# 9-Other_Inputs.net
KiCad netlist of a schematic drawn in Altium Designer
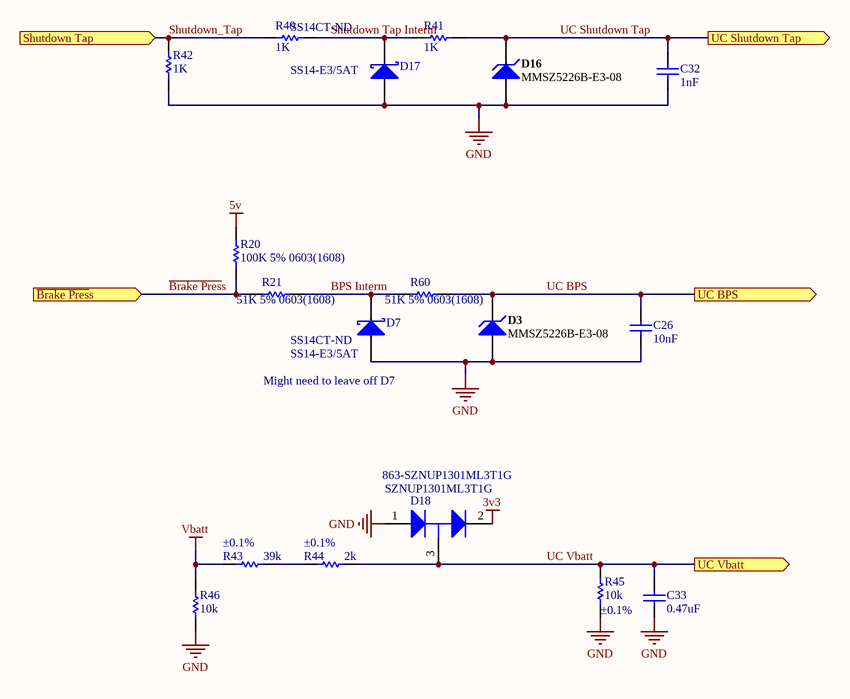
[diagram p0: 9-Other_Inputs.SchDoc]

(export (version "E")
  (design (tool "Eeschema 10.0.6"))
  (components
    (comp (ref "C26")
      (value "10nF")
      (footprint "1608[0603]")
      (description "Capacitor")
      (fields
        (field (name "MANUFACTURER") "Yageo")
        (field (name "MANUFACTURER PART NUMBER") "CC0603KRX7R9BB104")
      )
      (libsource (lib "Miscellaneous Devices") (part "Cap"))
    )
    (comp (ref "C32")
      (value "1nF")
      (footprint "1608[0603]")
      (description "Capacitor")
      (fields
        (field (name "MANUFACTURER") "Yageo")
        (field (name "MANUFACTURER PART NUMBER") "CC0603KRX7R9BB102")
      )
      (libsource (lib "Miscellaneous Devices") (part "Cap"))
    )
    (comp (ref "C33")
      (value "0.47uF")
      (footprint "1608[0603]")
      (description "Capacitor")
      (fields
        (field (name "MANUFACTURER") "Yageo")
        (field (name "MANUFACTURER PART NUMBER") "CC0603KRX7R8BB474")
      )
      (libsource (lib "Miscellaneous Devices") (part "Cap"))
    )
    (comp (ref "D3")
      (value "MMSZ5226B-E3-08")
      (footprint "VISH-SOD-123-2_V")
      (description "Small Signal Zener Diode, 3.3 V +/- 5%, -55 to 155 degC, 2-Pin SOD-123, RoHS, Tape and Reel")
      (fields (field (name "TOLERANCE") "+/- 5%") (field (name "MANUFACTURER") "Vishay Semiconductor"))
      (libsource (lib "Altium Content Vault") (part "VISH-DZEN_A1K2-2"))
    )
    (comp (ref "D7")
      (value "SS14-E3/5AT")
      (footprint "VISH-DO-214AC-2_V")
      (fields
        (field (name "MANUFACTURER") "Vishay Semiconductor")
        (field (name "SUPPLIER PART NUMBER 1") "SS14CT-ND")
      )
      (libsource (lib "Altium Content Vault") (part "VISH-DSKY_A1K2-2"))
    )
    (comp (ref "D16")
      (value "MMSZ5226B-E3-08")
      (footprint "VISH-SOD-123-2_V")
      (description "Small Signal Zener Diode, 3.3 V +/- 5%, -55 to 155 degC, 2-Pin SOD-123, RoHS, Tape and Reel")
      (fields (field (name "TOLERANCE") "+/- 5%") (field (name "MANUFACTURER") "Vishay Semiconductor"))
      (libsource (lib "Altium Content Vault") (part "VISH-DZEN_A1K2-2"))
    )
    (comp (ref "D17")
      (value "SS14-E3/5AT")
      (footprint "VISH-DO-214AC-2_V")
      (fields
        (field (name "MANUFACTURER") "Vishay Semiconductor")
        (field (name "SUPPLIER PART NUMBER 1") "SS14CT-ND")
      )
      (libsource (lib "Altium Content Vault") (part "VISH-DSKY_A1K2-2"))
    )
    (comp (ref "D18")
      (value "SZNUP1301ML3T1G")
      (footprint "ONSC-SOT-23-3-318-08_V")
      (fields
        (field (name "MANUFACTURER") "On Semiconductor")
        (field (name "SUPPLIER PART NUMBER 1") "863-SZNUP1301ML3T1G")
      )
      (libsource (lib "Altium Content Vault") (part "ONSC-NUP1301-SOT-23-3-318-08"))
    )
    (comp (ref "R20")
      (value "100K 5% 0603(1608)")
      (footprint "RESC0603(1608)_N")
      (description "100K 0.1W 5% 0603 (1608 Metric)  SMD")
      (fields (field (name "TOLERANCE") "5 %") (field (name "POWER") "0.1 W"))
      (libsource (lib "Altium Content Vault") (part "RES"))
    )
    (comp (ref "R21")
      (value "51K 5% 0603(1608)")
      (footprint "RESC0603(1608)_N")
      (description "51K 0.1W 5% 0603 (1608 Metric)  SMD")
      (fields (field (name "POWER") "0.1 W") (field (name "TOLERANCE") "5 %"))
      (libsource (lib "Altium Content Vault") (part "RES"))
    )
    (comp (ref "R40")
      (value "1K")
      (footprint "1608[0603]")
      (description "Resistor")
      (fields
        (field (name "MANUFACTURER") "Panasonic Electronic Components")
        (field (name "MANUFACTURER PART NUMBER") "ERJ-PA3F1001V")
      )
      (libsource (lib "Miscellaneous Devices") (part "Res1"))
    )
    (comp (ref "R41")
      (value "1K")
      (footprint "1608[0603]")
      (description "Resistor")
      (fields
        (field (name "MANUFACTURER") "Panasonic Electronic Components")
        (field (name "MANUFACTURER PART NUMBER") "ERJ-PA3F1001V")
      )
      (libsource (lib "Miscellaneous Devices") (part "Res1"))
    )
    (comp (ref "R42")
      (value "1K")
      (footprint "1608[0603]")
      (description "Resistor")
      (fields
        (field (name "MANUFACTURER") "Panasonic Electronic Components")
        (field (name "MANUFACTURER PART NUMBER") "ERJ-PA3F1001V")
      )
      (libsource (lib "Miscellaneous Devices") (part "Res1"))
    )
    (comp (ref "R43")
      (value "39k")
      (footprint "1608[0603]")
      (description "Resistor")
      (fields
        (field (name "MANUFACTURER") "Yageo")
        (field (name "MANUFACTURER PART NUMBER") "RT0603BRD0739KL")
        (field (name "TOLERANCE") "±0.1%")
      )
      (libsource (lib "Miscellaneous Devices") (part "Res1"))
    )
    (comp (ref "R44")
      (value "2k")
      (footprint "1608[0603]")
      (description "Resistor")
      (fields
        (field (name "MANUFACTURER") "Yageo")
        (field (name "MANUFACTURER PART NUMBER") "AT0603BRD072KL")
        (field (name "TOLERANCE") "±0.1%")
      )
      (libsource (lib "Miscellaneous Devices") (part "Res1"))
    )
    (comp (ref "R45")
      (value "10k")
      (footprint "1608[0603]")
      (description "Resistor")
      (fields
        (field (name "MANUFACTURER") "Yageo")
        (field (name "MANUFACTURER PART NUMBER") "RT0603BRD0710KL")
        (field (name "TOLERANCE") "±0.1%")
      )
      (libsource (lib "Miscellaneous Devices") (part "Res1"))
    )
    (comp (ref "R46")
      (value "10k")
      (footprint "1608[0603]")
      (description "Resistor")
      (fields
        (field (name "MANUFACTURER") "Yageo")
        (field (name "MANUFACTURER PART NUMBER") "RC0603JR-0710KL")
      )
      (libsource (lib "Miscellaneous Devices") (part "Res1"))
    )
    (comp (ref "R60")
      (value "51K 5% 0603(1608)")
      (footprint "RESC0603(1608)_N")
      (description "51K 0.1W 5% 0603 (1608 Metric)  SMD")
      (fields (field (name "POWER") "0.1 W") (field (name "TOLERANCE") "5 %"))
      (libsource (lib "Altium Content Vault") (part "RES"))
    )
  )
  (nets
    (net (code "1") (name "/BPS Interm") (class "Default")
      (node (ref "D7") (pin "2") (pinfunction "K_2") (pintype "passive"))
      (node (ref "R21") (pin "2") (pinfunction "2_2") (pintype "passive"))
      (node (ref "R60") (pin "1") (pinfunction "1_1") (pintype "passive"))
    )
    (net (code "2") (name "/Shutdown Tap Interm") (class "Default")
      (node (ref "D17") (pin "2") (pinfunction "K_2") (pintype "passive"))
      (node (ref "R40") (pin "1") (pinfunction "1_1") (pintype "passive"))
      (node (ref "R41") (pin "2") (pinfunction "2_2") (pintype "passive"))
    )
    (net (code "3") (name "/Shutdown_Tap") (class "Default")
      (node (ref "R40") (pin "2") (pinfunction "2_2") (pintype "passive"))
      (node (ref "R42") (pin "2") (pinfunction "2_2") (pintype "passive"))
    )
    (net (code "4") (name "/UC BPS") (class "Default")
      (node (ref "C26") (pin "2") (pinfunction "2_2") (pintype "passive"))
      (node (ref "D3") (pin "2") (pinfunction "K_2") (pintype "passive"))
      (node (ref "R60") (pin "2") (pinfunction "2_2") (pintype "passive"))
    )
    (net (code "5") (name "/UC Shutdown Tap") (class "Default")
      (node (ref "C32") (pin "2") (pinfunction "2_2") (pintype "passive"))
      (node (ref "D16") (pin "2") (pinfunction "K_2") (pintype "passive"))
      (node (ref "R41") (pin "1") (pinfunction "1_1") (pintype "passive"))
    )
    (net (code "6") (name "/UC Vbatt") (class "Default")
      (node (ref "C33") (pin "2") (pinfunction "2_2") (pintype "passive"))
      (node (ref "D18") (pin "3") (pinfunction "K/A_3") (pintype "passive"))
      (node (ref "R44") (pin "2") (pinfunction "2_2") (pintype "passive"))
      (node (ref "R45") (pin "2") (pinfunction "2_2") (pintype "passive"))
    )
    (net (code "7") (name "/~{Brake Pres}s") (class "Default")
      (node (ref "R20") (pin "1") (pinfunction "1_1") (pintype "passive"))
      (node (ref "R21") (pin "1") (pinfunction "1_1") (pintype "passive"))
    )
    (net (code "8") (name "3v3") (class "Default")
      (node (ref "D18") (pin "2") (pinfunction "K_2") (pintype "passive"))
    )
    (net (code "9") (name "5v") (class "Default")
      (node (ref "R20") (pin "2") (pinfunction "2_2") (pintype "passive"))
    )
    (net (code "10") (name "GND") (class "Default")
      (node (ref "C26") (pin "1") (pinfunction "1_1") (pintype "passive"))
      (node (ref "C32") (pin "1") (pinfunction "1_1") (pintype "passive"))
      (node (ref "C33") (pin "1") (pinfunction "1_1") (pintype "passive"))
      (node (ref "D16") (pin "1") (pinfunction "A_1") (pintype "passive"))
      (node (ref "D17") (pin "1") (pinfunction "A_1") (pintype "passive"))
      (node (ref "D18") (pin "1") (pinfunction "A_1") (pintype "passive"))
      (node (ref "D3") (pin "1") (pinfunction "A_1") (pintype "passive"))
      (node (ref "D7") (pin "1") (pinfunction "A_1") (pintype "passive"))
      (node (ref "R42") (pin "1") (pinfunction "1_1") (pintype "passive"))
      (node (ref "R45") (pin "1") (pinfunction "1_1") (pintype "passive"))
      (node (ref "R46") (pin "1") (pinfunction "1_1") (pintype "passive"))
    )
    (net (code "11") (name "Net-(R43-Pad2)") (class "Default")
      (node (ref "R43") (pin "2") (pinfunction "2_2") (pintype "passive"))
      (node (ref "R44") (pin "1") (pinfunction "1_1") (pintype "passive"))
    )
    (net (code "12") (name "Vbatt") (class "Default")
      (node (ref "R43") (pin "1") (pinfunction "1_1") (pintype "passive"))
      (node (ref "R46") (pin "2") (pinfunction "2_2") (pintype "passive"))
    )
  )
)
